# forkGuard_sensor_board.net
KiCad netlist of a schematic drawn in EasyEDA Pro
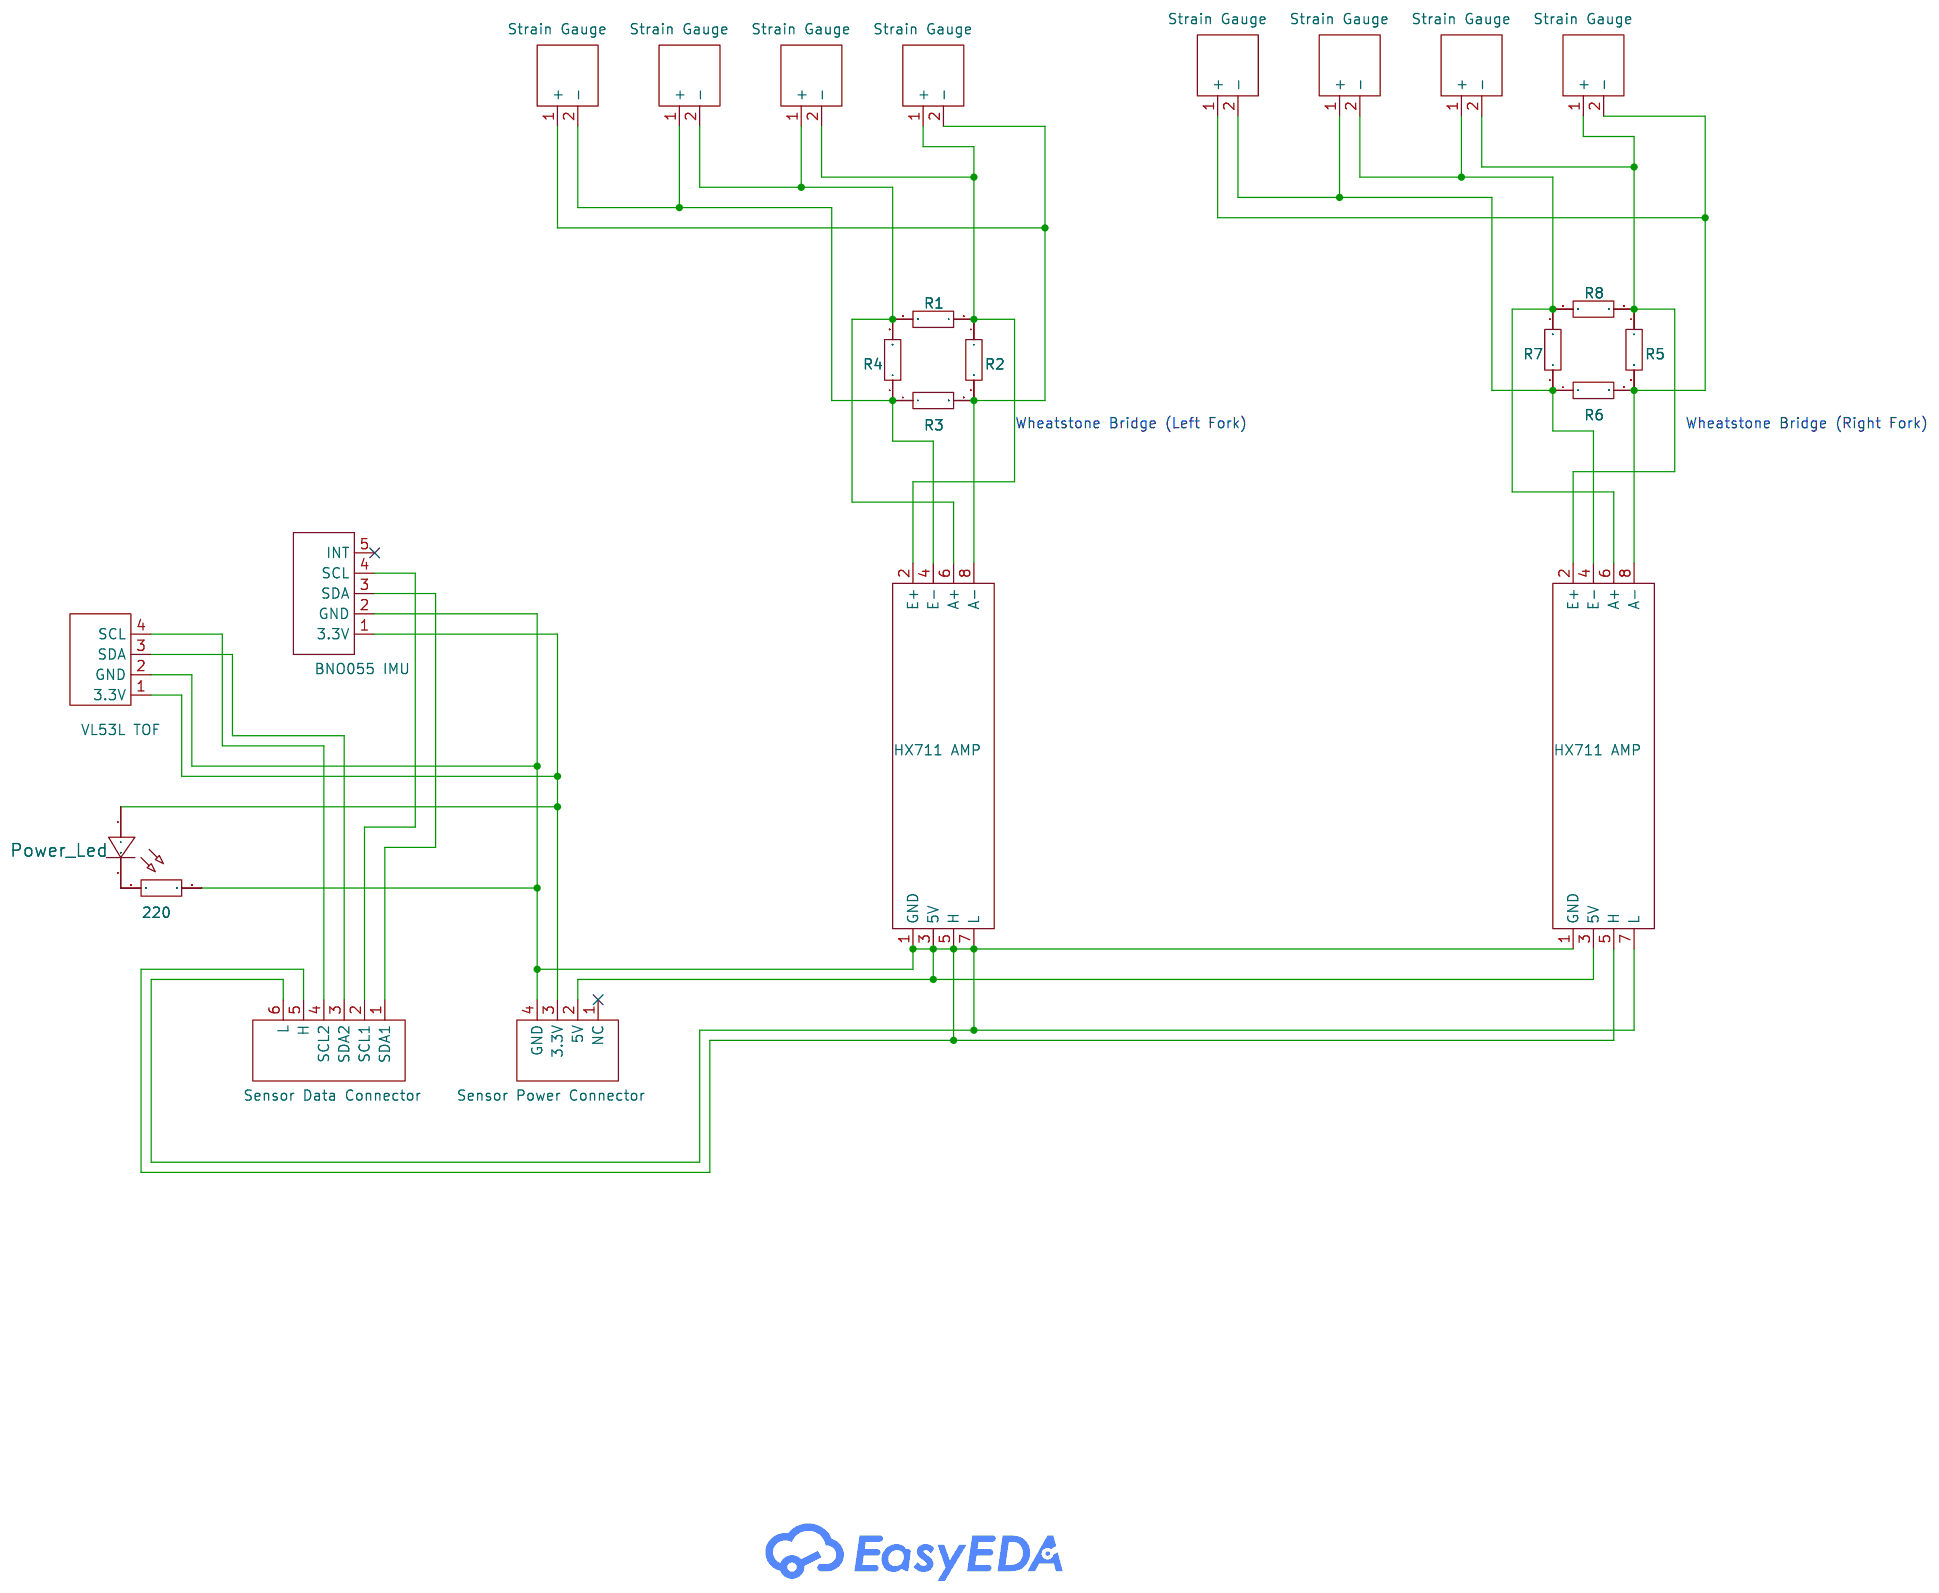
[diagram p0: schematic sheet]

(export (version "E")
  (design (tool "Eeschema 10.0.6"))
  (components
    (comp (ref "H1")
      (value "Sensor Data Connector")
      (footprint "easyedapro:HDR-TH_TW-06-01-T-S-150-085")
      (fields
        (field (name "Manufacturer Part") "TW-06-08-L-S-580-150")
        (field (name "Manufacturer") "SAMTEC")
      )
      (libsource (lib "easyedapro") (part "TW-06-08-L-S-580-150"))
    )
    (comp (ref "H2")
      (value "Sensor Power Connector")
      (footprint "easyedapro:HDR-TH_TW-04-06-T-S-433-120")
      (fields
        (field (name "Manufacturer Part") "TW-04-05-L-S-275-158")
        (field (name "Manufacturer") "SAMTEC")
      )
      (libsource (lib "easyedapro") (part "TW-04-05-L-S-275-158"))
    )
    (comp (ref "H3")
      (value "BNO055 IMU")
      (footprint "easyedapro:HDR-TH_TW-05-01-T-S-187-070")
      (fields
        (field (name "Manufacturer Part") "TW-05-01-T-S-187-070")
        (field (name "Manufacturer") "SAMTEC")
      )
      (libsource (lib "easyedapro") (part "TW-05-01-T-S-187-070"))
    )
    (comp (ref "H4")
      (value "HX711 AMP")
      (footprint "easyedapro:HDR-TH_8P-P2.00-V-M-R2-C4-S2.00-2")
      (fields
        (field (name "Manufacturer Part") "TW-04-04-L-D-277-109")
        (field (name "Manufacturer") "SAMTEC")
      )
      (libsource (lib "easyedapro") (part "TW-04-04-L-D-277-109"))
    )
    (comp (ref "H5")
      (value "HX711 AMP")
      (footprint "easyedapro:HDR-TH_8P-P2.00-V-M-R2-C4-S2.00-2")
      (fields
        (field (name "Manufacturer Part") "TW-04-04-L-D-277-109")
        (field (name "Manufacturer") "SAMTEC")
      )
      (libsource (lib "easyedapro") (part "TW-04-04-L-D-277-109"))
    )
    (comp (ref "H6")
      (value "VL53L TOF")
      (footprint "easyedapro:HDR-TH_4P-P2.00-V-M_TW-04-02-T-S-195-090")
      (fields
        (field (name "Manufacturer Part") "TW-04-02-L-S-125-100")
        (field (name "Manufacturer") "SAMTEC")
      )
      (libsource (lib "easyedapro") (part "TW-04-02-L-S-125-100"))
    )
    (comp (ref "H11")
      (value "Strain Gauge")
      (footprint "easyedapro:HDR-TH_TW-02-03-G-S-245-155")
      (fields
        (field (name "Manufacturer Part") "TW-02-03-G-S-245-155")
        (field (name "Manufacturer") "SAMTEC")
      )
      (libsource (lib "easyedapro") (part "TW-02-03-G-S-245-155"))
    )
    (comp (ref "H12")
      (value "Strain Gauge")
      (footprint "easyedapro:HDR-TH_TW-02-03-G-S-245-155")
      (fields
        (field (name "Manufacturer Part") "TW-02-03-G-S-245-155")
        (field (name "Manufacturer") "SAMTEC")
      )
      (libsource (lib "easyedapro") (part "TW-02-03-G-S-245-155"))
    )
    (comp (ref "H13")
      (value "Strain Gauge")
      (footprint "easyedapro:HDR-TH_TW-02-03-G-S-245-155")
      (fields
        (field (name "Manufacturer Part") "TW-02-03-G-S-245-155")
        (field (name "Manufacturer") "SAMTEC")
      )
      (libsource (lib "easyedapro") (part "TW-02-03-G-S-245-155"))
    )
    (comp (ref "H14")
      (value "Strain Gauge")
      (footprint "easyedapro:HDR-TH_TW-02-03-G-S-245-155")
      (fields
        (field (name "Manufacturer Part") "TW-02-03-G-S-245-155")
        (field (name "Manufacturer") "SAMTEC")
      )
      (libsource (lib "easyedapro") (part "TW-02-03-G-S-245-155"))
    )
    (comp (ref "H15")
      (value "Strain Gauge")
      (footprint "easyedapro:HDR-TH_TW-02-03-G-S-245-155")
      (fields
        (field (name "Manufacturer Part") "TW-02-03-G-S-245-155")
        (field (name "Manufacturer") "SAMTEC")
      )
      (libsource (lib "easyedapro") (part "TW-02-03-G-S-245-155"))
    )
    (comp (ref "H16")
      (value "Strain Gauge")
      (footprint "easyedapro:HDR-TH_TW-02-03-G-S-245-155")
      (fields
        (field (name "Manufacturer Part") "TW-02-03-G-S-245-155")
        (field (name "Manufacturer") "SAMTEC")
      )
      (libsource (lib "easyedapro") (part "TW-02-03-G-S-245-155"))
    )
    (comp (ref "H17")
      (value "Strain Gauge")
      (footprint "easyedapro:HDR-TH_TW-02-03-G-S-245-155")
      (fields
        (field (name "Manufacturer Part") "TW-02-03-G-S-245-155")
        (field (name "Manufacturer") "SAMTEC")
      )
      (libsource (lib "easyedapro") (part "TW-02-03-G-S-245-155"))
    )
    (comp (ref "H18")
      (value "Strain Gauge")
      (footprint "easyedapro:HDR-TH_TW-02-03-G-S-245-155")
      (fields
        (field (name "Manufacturer Part") "TW-02-03-G-S-245-155")
        (field (name "Manufacturer") "SAMTEC")
      )
      (libsource (lib "easyedapro") (part "TW-02-03-G-S-245-155"))
    )
    (comp (ref "Power_Led")
      (value "~")
      (footprint "easyedapro:LED0402-RD_YELLOW")
      (libsource (lib "easyedapro") (part "LED_R"))
    )
    (comp (ref "R1") (value "10K") (footprint "easyedapro:R0603") (libsource (lib "easyedapro") (part "Res")))
    (comp (ref "R2") (value "10K") (footprint "easyedapro:R0603") (libsource (lib "easyedapro") (part "Res")))
    (comp (ref "R3") (value "10K") (footprint "easyedapro:R0603") (libsource (lib "easyedapro") (part "Res")))
    (comp (ref "R4") (value "10K") (footprint "easyedapro:R0603") (libsource (lib "easyedapro") (part "Res")))
    (comp (ref "R5") (value "10K") (footprint "easyedapro:R0603") (libsource (lib "easyedapro") (part "Res")))
    (comp (ref "R6") (value "10K") (footprint "easyedapro:R0603") (libsource (lib "easyedapro") (part "Res")))
    (comp (ref "R7") (value "10K") (footprint "easyedapro:R0603") (libsource (lib "easyedapro") (part "Res")))
    (comp (ref "R8") (value "10K") (footprint "easyedapro:R0603") (libsource (lib "easyedapro") (part "Res")))
    (comp (ref "R9") (value "10K") (footprint "easyedapro:R0603") (libsource (lib "easyedapro") (part "Res")))
  )
  (nets
    (net (code "1") (name "Net-(H1-H)") (class "Default")
      (node (ref "H1") (pin "5") (pinfunction "H_5") (pintype "unspecified"))
      (node (ref "H1") (pin "6") (pinfunction "L_6") (pintype "unspecified"))
      (node (ref "H2") (pin "2") (pinfunction "5V_2") (pintype "unspecified"))
      (node (ref "H2") (pin "4") (pinfunction "GND_4") (pintype "unspecified"))
      (node (ref "H3") (pin "2") (pinfunction "GND_2") (pintype "unspecified"))
      (node (ref "H4") (pin "1") (pinfunction "GND_1") (pintype "unspecified"))
      (node (ref "H4") (pin "3") (pinfunction "5V_3") (pintype "unspecified"))
      (node (ref "H4") (pin "5") (pinfunction "H_5") (pintype "unspecified"))
      (node (ref "H4") (pin "7") (pinfunction "L_7") (pintype "unspecified"))
      (node (ref "H5") (pin "1") (pinfunction "GND_1") (pintype "unspecified"))
      (node (ref "H5") (pin "3") (pinfunction "5V_3") (pintype "unspecified"))
      (node (ref "H5") (pin "5") (pinfunction "H_5") (pintype "unspecified"))
      (node (ref "H5") (pin "7") (pinfunction "L_7") (pintype "unspecified"))
      (node (ref "H6") (pin "2") (pinfunction "GND_2") (pintype "unspecified"))
      (node (ref "R9") (pin "2") (pinfunction "2_2") (pintype "input"))
    )
    (net (code "2") (name "Net-(H1-SCL1)") (class "Default")
      (node (ref "H1") (pin "2") (pinfunction "SCL1_2") (pintype "unspecified"))
      (node (ref "H3") (pin "4") (pinfunction "SCL_4") (pintype "unspecified"))
    )
    (net (code "3") (name "Net-(H1-SCL2)") (class "Default")
      (node (ref "H1") (pin "4") (pinfunction "SCL2_4") (pintype "unspecified"))
      (node (ref "H6") (pin "4") (pinfunction "SCL_4") (pintype "unspecified"))
    )
    (net (code "4") (name "Net-(H1-SDA1)") (class "Default")
      (node (ref "H1") (pin "1") (pinfunction "SDA1_1") (pintype "unspecified"))
      (node (ref "H3") (pin "3") (pinfunction "SDA_3") (pintype "unspecified"))
    )
    (net (code "5") (name "Net-(H1-SDA2)") (class "Default")
      (node (ref "H1") (pin "3") (pinfunction "SDA2_3") (pintype "unspecified"))
      (node (ref "H6") (pin "3") (pinfunction "SDA_3") (pintype "unspecified"))
    )
    (net (code "6") (name "Net-(H2-3.3V)") (class "Default")
      (node (ref "H2") (pin "3") (pinfunction "3.3V_3") (pintype "unspecified"))
      (node (ref "H3") (pin "1") (pinfunction "3.3V_1") (pintype "unspecified"))
      (node (ref "H6") (pin "1") (pinfunction "3.3V_1") (pintype "unspecified"))
      (node (ref "Power_Led") (pin "1") (pinfunction "A_1") (pintype "input"))
    )
    (net (code "7") (name "Net-(H11-+)") (class "Default")
      (node (ref "H11") (pin "1") (pinfunction "+_1") (pintype "unspecified"))
      (node (ref "H12") (pin "2") (pinfunction "-_2") (pintype "unspecified"))
      (node (ref "H5") (pin "2") (pinfunction "E+_2") (pintype "unspecified"))
      (node (ref "R1") (pin "1") (pinfunction "1_1") (pintype "input"))
      (node (ref "R2") (pin "1") (pinfunction "1_1") (pintype "input"))
    )
    (net (code "8") (name "Net-(H11--)") (class "Default")
      (node (ref "H11") (pin "2") (pinfunction "-_2") (pintype "unspecified"))
      (node (ref "H14") (pin "1") (pinfunction "+_1") (pintype "unspecified"))
      (node (ref "H5") (pin "8") (pinfunction "A-_8") (pintype "unspecified"))
      (node (ref "R2") (pin "2") (pinfunction "2_2") (pintype "input"))
      (node (ref "R3") (pin "2") (pinfunction "2_2") (pintype "input"))
    )
    (net (code "9") (name "Net-(H12-+)") (class "Default")
      (node (ref "H12") (pin "1") (pinfunction "+_1") (pintype "unspecified"))
      (node (ref "H13") (pin "2") (pinfunction "-_2") (pintype "unspecified"))
      (node (ref "H5") (pin "6") (pinfunction "A+_6") (pintype "unspecified"))
      (node (ref "R1") (pin "2") (pinfunction "2_2") (pintype "input"))
      (node (ref "R4") (pin "2") (pinfunction "2_2") (pintype "input"))
    )
    (net (code "10") (name "Net-(H13-+)") (class "Default")
      (node (ref "H13") (pin "1") (pinfunction "+_1") (pintype "unspecified"))
      (node (ref "H14") (pin "2") (pinfunction "-_2") (pintype "unspecified"))
      (node (ref "H5") (pin "4") (pinfunction "E-_4") (pintype "unspecified"))
      (node (ref "R3") (pin "1") (pinfunction "1_1") (pintype "input"))
      (node (ref "R4") (pin "1") (pinfunction "1_1") (pintype "input"))
    )
    (net (code "11") (name "Net-(H15-+)") (class "Default")
      (node (ref "H15") (pin "1") (pinfunction "+_1") (pintype "unspecified"))
      (node (ref "H16") (pin "2") (pinfunction "-_2") (pintype "unspecified"))
      (node (ref "H4") (pin "2") (pinfunction "E+_2") (pintype "unspecified"))
      (node (ref "R5") (pin "1") (pinfunction "1_1") (pintype "input"))
      (node (ref "R8") (pin "1") (pinfunction "1_1") (pintype "input"))
    )
    (net (code "12") (name "Net-(H15--)") (class "Default")
      (node (ref "H15") (pin "2") (pinfunction "-_2") (pintype "unspecified"))
      (node (ref "H18") (pin "1") (pinfunction "+_1") (pintype "unspecified"))
      (node (ref "H4") (pin "8") (pinfunction "A-_8") (pintype "unspecified"))
      (node (ref "R5") (pin "2") (pinfunction "2_2") (pintype "input"))
      (node (ref "R6") (pin "2") (pinfunction "2_2") (pintype "input"))
    )
    (net (code "13") (name "Net-(H16-+)") (class "Default")
      (node (ref "H16") (pin "1") (pinfunction "+_1") (pintype "unspecified"))
      (node (ref "H17") (pin "2") (pinfunction "-_2") (pintype "unspecified"))
      (node (ref "H4") (pin "6") (pinfunction "A+_6") (pintype "unspecified"))
      (node (ref "R7") (pin "2") (pinfunction "2_2") (pintype "input"))
      (node (ref "R8") (pin "2") (pinfunction "2_2") (pintype "input"))
    )
    (net (code "14") (name "Net-(H17-+)") (class "Default")
      (node (ref "H17") (pin "1") (pinfunction "+_1") (pintype "unspecified"))
      (node (ref "H18") (pin "2") (pinfunction "-_2") (pintype "unspecified"))
      (node (ref "H4") (pin "4") (pinfunction "E-_4") (pintype "unspecified"))
      (node (ref "R6") (pin "1") (pinfunction "1_1") (pintype "input"))
      (node (ref "R7") (pin "1") (pinfunction "1_1") (pintype "input"))
    )
    (net (code "15") (name "Net-(Power_Led-C)") (class "Default")
      (node (ref "Power_Led") (pin "2") (pinfunction "C_2") (pintype "input"))
      (node (ref "R9") (pin "1") (pinfunction "1_1") (pintype "input"))
    )
    (net (code "16") (name "unconnected-(H2-NC-Pad1)") (class "Default")
      (node (ref "H2") (pin "1") (pinfunction "NC_1") (pintype "unspecified+no_connect"))
    )
    (net (code "17") (name "unconnected-(H3-INT-Pad5)") (class "Default")
      (node (ref "H3") (pin "5") (pinfunction "INT_5") (pintype "unspecified+no_connect"))
    )
  )
)
